# 00_ESP8266_CH340.net
KiCad netlist of a schematic drawn in Altium Designer
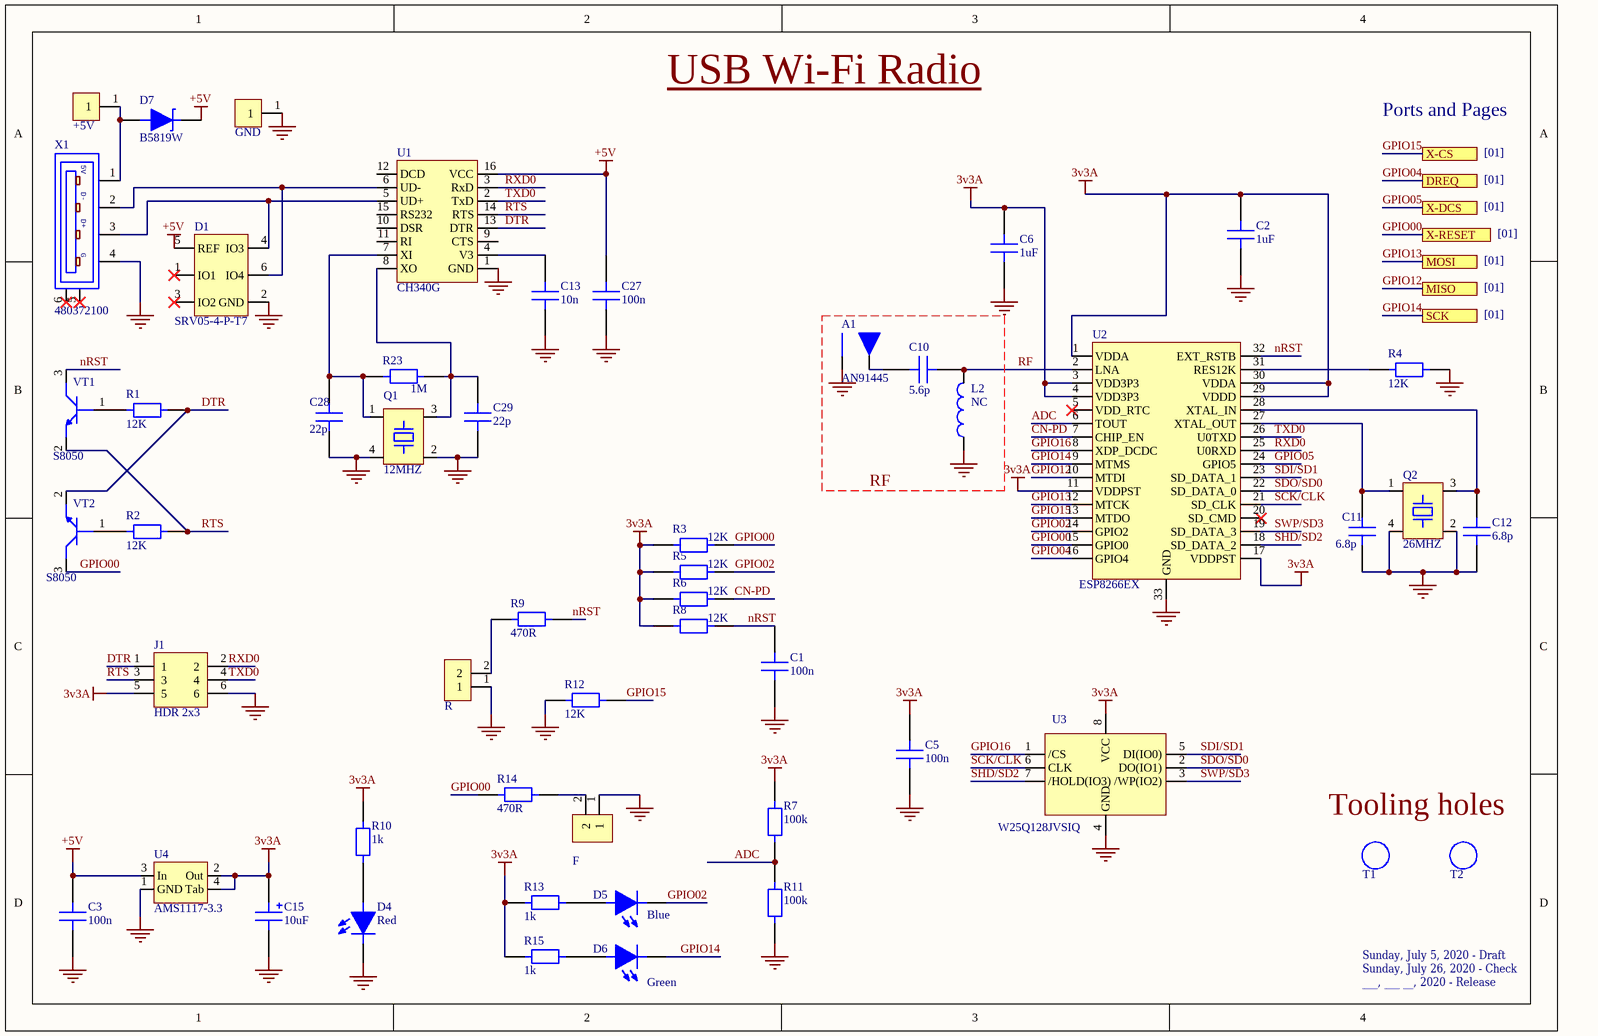
[diagram p0: [00] ESP8266 CH340.SchDoc]

(export (version "E")
  (design (tool "Eeschema 10.0.6"))
  (components
    (comp (ref "A1")
      (value "AN91445")
      (footprint "MIFA 2.4GHz")
      (libsource (lib "WiFi_Lib") (part "MIFA 2.4GHz"))
    )
    (comp (ref "C1")
      (value "100n")
      (footprint "0603 CAP")
      (description "MULTILAYER CERAMIC CAPACITORS MLCC - SMD/SMT 100NF 50V 0603 ROHS")
      (fields (field (name "MANUFACTURER") "YAGEO") (field (name "MFR.PART #") "CC0603KRX7R9BB104"))
      (libsource (lib "JLC_Lib") (part "CC0603KRX7R9BB104"))
    )
    (comp (ref "C2")
      (value "1uF")
      (footprint "0402")
      (description "MULTILAYER CERAMIC CAPACITORS MLCC - SMD/SMT 1UF 25V 0402 ROHS")
      (fields
        (field (name "MANUFACTURER") "Samsung Electro-Mechanics")
        (field (name "MFR.PART #") "CL05A105KA5NQNC")
      )
      (libsource (lib "JLC_Lib") (part "CL05A105KA5NQNC"))
    )
    (comp (ref "C3")
      (value "100n")
      (footprint "0603 CAP")
      (description "MULTILAYER CERAMIC CAPACITORS MLCC - SMD/SMT 100NF 50V 0603 ROHS")
      (fields (field (name "MANUFACTURER") "YAGEO") (field (name "MFR.PART #") "CC0603KRX7R9BB104"))
      (libsource (lib "JLC_Lib") (part "CC0603KRX7R9BB104"))
    )
    (comp (ref "C5")
      (value "100n")
      (footprint "0603 CAP")
      (description "MULTILAYER CERAMIC CAPACITORS MLCC - SMD/SMT 100NF 50V 0603 ROHS")
      (fields (field (name "MANUFACTURER") "YAGEO") (field (name "MFR.PART #") "CC0603KRX7R9BB104"))
      (libsource (lib "JLC_Lib") (part "CC0603KRX7R9BB104"))
    )
    (comp (ref "C6")
      (value "1uF")
      (footprint "0402")
      (description "MULTILAYER CERAMIC CAPACITORS MLCC - SMD/SMT 1UF 25V 0402 ROHS")
      (fields
        (field (name "MANUFACTURER") "Samsung Electro-Mechanics")
        (field (name "MFR.PART #") "CL05A105KA5NQNC")
      )
      (libsource (lib "JLC_Lib") (part "CL05A105KA5NQNC"))
    )
    (comp (ref "C10")
      (value "5.6p")
      (footprint "CAP 0402")
      (description "5.6PF ±0.25PF 50V C0G 0402 MULTILAYER CERAMIC CAPACITORS MLCC - SMD/SMT ROHS")
      (fields
        (field (name "MANUFACTURER") "Samsung Electro-Mechanics")
        (field (name "MFR.PART #") "CL05C5R6CB5NNNC")
      )
      (libsource (lib "JLC_Lib") (part "CL05B103KB5NNNC_1"))
    )
    (comp (ref "C11")
      (value "6.8p")
      (footprint "0402")
      (description "MULTILAYER CERAMIC CAPACITORS MLCC - SMD/SMT 6.8PF 50V 0402 ROHS")
      (fields
        (field (name "MANUFACTURER") "Guangdong Fenghua Advanced Tech")
        (field (name "MFR.PART #") "0402CG6R8C500NT")
      )
      (libsource (lib "JLC_Lib") (part "0402CG6R8C500NT"))
    )
    (comp (ref "C12")
      (value "6.8p")
      (footprint "0402")
      (description "MULTILAYER CERAMIC CAPACITORS MLCC - SMD/SMT 6.8PF 50V 0402 ROHS")
      (fields
        (field (name "MANUFACTURER") "Guangdong Fenghua Advanced Tech")
        (field (name "MFR.PART #") "0402CG6R8C500NT")
      )
      (libsource (lib "JLC_Lib") (part "0402CG6R8C500NT"))
    )
    (comp (ref "C13")
      (value "10n")
      (footprint "0603 CAP")
      (description "MULTILAYER CERAMIC CAPACITORS MLCC - SMD/SMT 10NF 50V 0603 ROHS")
      (fields
        (field (name "MANUFACTURER") "Guangdong Fenghua Advanced Tech")
        (field (name "MFR.PART #") "0603B103K500NT")
      )
      (libsource (lib "JLC_Lib") (part "0603B103K500NT"))
    )
    (comp (ref "C15")
      (value "10uF")
      (footprint "CAP 1206")
      (description "TANTALUM CAPACITORS 10UF 16V CASE-A_3216 ROHS")
      (fields (field (name "MANUFACTURER") "AVX") (field (name "MFR.PART #") "TAJA106K016RNJ"))
      (libsource (lib "JLC_Lib") (part "TAJA106K016RNJ"))
    )
    (comp (ref "C27")
      (value "100n")
      (footprint "0603 CAP")
      (description "MULTILAYER CERAMIC CAPACITORS MLCC - SMD/SMT 100NF 50V 0603 ROHS")
      (fields (field (name "MANUFACTURER") "YAGEO") (field (name "MFR.PART #") "CC0603KRX7R9BB104"))
      (libsource (lib "JLC_Lib") (part "CC0603KRX7R9BB104"))
    )
    (comp (ref "C28")
      (value "22p")
      (footprint "0603 CAP")
      (description "MULTILAYER CERAMIC CAPACITORS MLCC - SMD/SMT 22PF 50V 0603 ROHS")
      (fields
        (field (name "MANUFACTURER") "Samsung Electro-Mechanics")
        (field (name "MFR.PART #") "CL10C220JB8NNNC")
      )
      (libsource (lib "JLC_Lib") (part "CL10C220JB8NNNC"))
    )
    (comp (ref "C29")
      (value "22p")
      (footprint "0603 CAP")
      (description "MULTILAYER CERAMIC CAPACITORS MLCC - SMD/SMT 22PF 50V 0603 ROHS")
      (fields
        (field (name "MANUFACTURER") "Samsung Electro-Mechanics")
        (field (name "MFR.PART #") "CL10C220JB8NNNC")
      )
      (libsource (lib "JLC_Lib") (part "CL10C220JB8NNNC"))
    )
    (comp (ref "D1")
      (value "SRV05-4-P-T7")
      (footprint "SOT-23-6")
      (description "TVS SOT-23-6 ROHS")
      (fields (field (name "MANUFACTURER") "ProTek Devices") (field (name "LCSC PART #") "C85364"))
      (libsource (lib "JLC_Lib") (part "SRV05-4-P-T7"))
    )
    (comp (ref "D4")
      (value "Red")
      (footprint "LED 0603")
      (description "LIGHT EMITTING DIODES (LED) RED 520~625NM 90~100MCD@20MA TOP VIEW 0603 ROHS")
      (fields (field (name "MANUFACTURER") "Hubei KENTO Elec") (field (name "MFR.PART #") "KT-0603R"))
      (libsource (lib "JLC_Lib") (part "KT-0603R"))
    )
    (comp (ref "D5")
      (value "Blue")
      (footprint "LED 0603")
      (description "LIGHT EMITTING DIODES (LED) BLUE 465~475NM 11.5~28.5MCD@5MA TOP VIEW 0603 ROHS")
      (fields
        (field (name "MANUFACTURER") "Everlight Elec")
        (field (name "MFR.PART #") "19-217/BHC-ZL1M2RY/3T")
      )
      (libsource (lib "JLC_Lib") (part "19-217/BHC-ZL1M2RY/3T"))
    )
    (comp (ref "D6")
      (value "Green")
      (footprint "LED 0603")
      (description "LIGHT EMITTING DIODES (LED) GREEN 520~535NM 112~258MCD@20MA TOP VIEW 0603 ROHS")
      (fields
        (field (name "MANUFACTURER") "Everlight Elec")
        (field (name "MFR.PART #") "19-217/GHC-YR1S2/3T")
      )
      (libsource (lib "JLC_Lib") (part "19-217/GHC-YR1S2/3T"))
    )
    (comp (ref "D7")
      (value "B5819W")
      (footprint "SOD-123")
      (description "SCHOTTKY BARRIER DIODES (SBD) SOD-123 ROHS")
      (fields
        (field (name "MANUFACTURER") "Changjiang Electronics Tech (CJ)")
        (field (name "LCSC PART #") "C8598")
      )
      (libsource (lib "JLC_Lib") (part "B5819W"))
    )
    (comp (ref "J1")
      (value "HDR 2x3")
      (footprint "HDR 2x3 2.54mm")
      (description "CONN HEADER 6POS .100 STR 30AU")
      (libsource (lib "WiFi_Lib") (part "67997-106HLF"))
    )
    (comp (ref "JP1")
      (value "R")
      (footprint "Hdr_Fem_1x2_2.54mm")
      (description "CONN HEADER VERT 2POS 2.54MM")
      (libsource (lib "") (part "68602-204HLF_1"))
    )
    (comp (ref "JP2")
      (value "F")
      (footprint "Hdr_Fem_1x2_2.54mm")
      (description "CONN HEADER VERT 2POS 2.54MM")
      (libsource (lib "WiFi_Lib") (part "68602-204HLF"))
    )
    (comp (ref "JP3")
      (value "+5V")
      (footprint "Hdr_Fem_1x1_2.54mm")
      (description "CONN HEADER VERT 1POS 2.54MM")
      (libsource (lib "WiFi_Lib") (part "68602-101HLF"))
    )
    (comp (ref "JP4")
      (value "GND")
      (footprint "Hdr_Fem_1x1_2.54mm")
      (description "CONN HEADER VERT 1POS 2.54MM")
      (libsource (lib "WiFi_Lib") (part "68602-101HLF"))
    )
    (comp (ref "L2")
      (value "NC")
      (footprint "IND 0402")
      (description "IND 0402 Matching")
      (libsource (lib "WiFi_Lib") (part "NC IND"))
    )
    (comp (ref "Q1")
      (value "12MHZ")
      (footprint "ABM8W")
      (description "SMD CRYSTAL RESONATORS 12MHZ ±10PPM SMD-3225_4P ROHS")
      (fields (field (name "MANUFACTURER") "Yangxing Tech") (field (name "MFR.PART #") "X322512MSB4SI"))
      (libsource (lib "JLC_Lib") (part "X322512MSB4SI"))
    )
    (comp (ref "Q2")
      (value "26MHZ")
      (footprint "ABM8W")
      (description "SMD CRYSTAL RESONATORS 26MHZ ±10PPM SMD-3225_4P ROHS")
      (fields (field (name "MANUFACTURER") "Yangxing Tech") (field (name "MFR.PART #") "X322526MEB4SC"))
      (libsource (lib "JLC_Lib") (part "X322526MEB4SC"))
    )
    (comp (ref "R1")
      (value "12K")
      (footprint "0603 RES")
      (description "CHIP RESISTOR - SURFACE MOUNT 12KOHMS ±1% 1/10W 0603 ROHS")
      (fields (field (name "MANUFACTURER") "Uniroyal Elec") (field (name "MFR.PART #") "0603WAF1202T5E"))
      (libsource (lib "JLC_Lib") (part "0603WAF1202T5E"))
    )
    (comp (ref "R2")
      (value "12K")
      (footprint "0603 RES")
      (description "CHIP RESISTOR - SURFACE MOUNT 12KOHMS ±1% 1/10W 0603 ROHS")
      (fields (field (name "MANUFACTURER") "Uniroyal Elec") (field (name "MFR.PART #") "0603WAF1202T5E"))
      (libsource (lib "JLC_Lib") (part "0603WAF1202T5E"))
    )
    (comp (ref "R3")
      (value "12K")
      (footprint "0603 RES")
      (description "CHIP RESISTOR - SURFACE MOUNT 12KOHMS ±1% 1/10W 0603 ROHS")
      (fields (field (name "MANUFACTURER") "Uniroyal Elec") (field (name "MFR.PART #") "0603WAF1202T5E"))
      (libsource (lib "JLC_Lib") (part "0603WAF1202T5E"))
    )
    (comp (ref "R4")
      (value "12K")
      (footprint "0402 RES")
      (description "CHIP RESISTOR - SURFACE MOUNT 12KOHMS ±1% 1/16W 0402 ROHS")
      (fields (field (name "MANUFACTURER") "Uniroyal Elec") (field (name "MFR.PART #") "0402WGF1202TCE"))
      (libsource (lib "JLC_Lib") (part "0402WGF1202TCE"))
    )
    (comp (ref "R5")
      (value "12K")
      (footprint "0603 RES")
      (description "CHIP RESISTOR - SURFACE MOUNT 12KOHMS ±1% 1/10W 0603 ROHS")
      (fields (field (name "MANUFACTURER") "Uniroyal Elec") (field (name "MFR.PART #") "0603WAF1202T5E"))
      (libsource (lib "JLC_Lib") (part "0603WAF1202T5E"))
    )
    (comp (ref "R6")
      (value "12K")
      (footprint "0603 RES")
      (description "CHIP RESISTOR - SURFACE MOUNT 12KOHMS ±1% 1/10W 0603 ROHS")
      (fields (field (name "MANUFACTURER") "Uniroyal Elec") (field (name "MFR.PART #") "0603WAF1202T5E"))
      (libsource (lib "JLC_Lib") (part "0603WAF1202T5E"))
    )
    (comp (ref "R7")
      (value "100k")
      (footprint "0603 RES")
      (description "CHIP RESISTOR - SURFACE MOUNT 100KOHMS ±1% 1/10W 0603 ROHS")
      (fields (field (name "MANUFACTURER") "Uniroyal Elec") (field (name "MFR.PART #") "0603WAF1003T5E"))
      (libsource (lib "JLC_Lib") (part "0603WAF1003T5E"))
    )
    (comp (ref "R8")
      (value "12K")
      (footprint "0603 RES")
      (description "CHIP RESISTOR - SURFACE MOUNT 12KOHMS ±1% 1/10W 0603 ROHS")
      (fields (field (name "MANUFACTURER") "Uniroyal Elec") (field (name "MFR.PART #") "0603WAF1202T5E"))
      (libsource (lib "JLC_Lib") (part "0603WAF1202T5E"))
    )
    (comp (ref "R9")
      (value "470R")
      (footprint "0603 RES")
      (description "CHIP RESISTOR - SURFACE MOUNT 470OHMS ±1% 1/10W 0603 ROHS")
      (fields (field (name "MANUFACTURER") "Uniroyal Elec") (field (name "MFR.PART #") "0603WAF4700T5E"))
      (libsource (lib "JLC_Lib") (part "0603WAF4700T5E"))
    )
    (comp (ref "R10")
      (value "1k")
      (footprint "0603 RES")
      (description "CHIP RESISTOR - SURFACE MOUNT 1KOHMS ±1% 1/10W 0603 ROHS")
      (fields (field (name "MANUFACTURER") "Uniroyal Elec") (field (name "MFR.PART #") "0603WAF1001T5E"))
      (libsource (lib "JLC_Lib") (part "0603WAF1001T5E"))
    )
    (comp (ref "R11")
      (value "100k")
      (footprint "0603 RES")
      (description "CHIP RESISTOR - SURFACE MOUNT 100KOHMS ±1% 1/10W 0603 ROHS")
      (fields (field (name "MANUFACTURER") "Uniroyal Elec") (field (name "MFR.PART #") "0603WAF1003T5E"))
      (libsource (lib "JLC_Lib") (part "0603WAF1003T5E"))
    )
    (comp (ref "R12")
      (value "12K")
      (footprint "0603 RES")
      (description "CHIP RESISTOR - SURFACE MOUNT 12KOHMS ±1% 1/10W 0603 ROHS")
      (fields (field (name "MANUFACTURER") "Uniroyal Elec") (field (name "MFR.PART #") "0603WAF1202T5E"))
      (libsource (lib "JLC_Lib") (part "0603WAF1202T5E"))
    )
    (comp (ref "R13")
      (value "1k")
      (footprint "0603 RES")
      (description "CHIP RESISTOR - SURFACE MOUNT 1KOHMS ±1% 1/10W 0603 ROHS")
      (fields (field (name "MANUFACTURER") "Uniroyal Elec") (field (name "MFR.PART #") "0603WAF1001T5E"))
      (libsource (lib "JLC_Lib") (part "0603WAF1001T5E"))
    )
    (comp (ref "R14")
      (value "470R")
      (footprint "0603 RES")
      (description "CHIP RESISTOR - SURFACE MOUNT 470OHMS ±1% 1/10W 0603 ROHS")
      (fields (field (name "MANUFACTURER") "Uniroyal Elec") (field (name "MFR.PART #") "0603WAF4700T5E"))
      (libsource (lib "JLC_Lib") (part "0603WAF4700T5E"))
    )
    (comp (ref "R15")
      (value "1k")
      (footprint "0603 RES")
      (description "CHIP RESISTOR - SURFACE MOUNT 1KOHMS ±1% 1/10W 0603 ROHS")
      (fields (field (name "MANUFACTURER") "Uniroyal Elec") (field (name "MFR.PART #") "0603WAF1001T5E"))
      (libsource (lib "JLC_Lib") (part "0603WAF1001T5E"))
    )
    (comp (ref "R23")
      (value "1M")
      (footprint "0603 RES")
      (description "CHIP RESISTOR - SURFACE MOUNT 1MOHMS ±1% 1/10W 0603 ROHS")
      (fields (field (name "MANUFACTURER") "Uniroyal Elec") (field (name "MFR.PART #") "0603WAF1004T5E"))
      (libsource (lib "JLC_Lib") (part "0603WAF1004T5E"))
    )
    (comp (ref "T1")
      (value "Tooling hole")
      (footprint "Tooling")
      (description "For JLCPCB SMT Assembly")
      (libsource (lib "JLC_Lib") (part "Tooling hole"))
    )
    (comp (ref "T2")
      (value "Tooling hole")
      (footprint "Tooling")
      (description "For JLCPCB SMT Assembly")
      (libsource (lib "JLC_Lib") (part "Tooling hole"))
    )
    (comp (ref "U1")
      (value "CH340G")
      (footprint "SOP-16")
      (description "USB 2MBPS 3.3V, 5V SOP-16_150MIL ROHS")
      (fields (field (name "MANUFACTURER") "Jiangsu Qin Heng") (field (name "LCSC PART #") "C14267"))
      (libsource (lib "JLC_Lib") (part "CH340G"))
    )
    (comp (ref "U2")
      (value "ESP8266EX")
      (footprint "QFN-32 Thermal")
      (fields (field (name "MANUFACTURER") "Espressif Systems") (field (name "LCSC PART #") "C77967"))
      (libsource (lib "JLC_Lib") (part "ESP8266EX"))
    )
    (comp (ref "U3")
      (value "W25Q128JVSIQ")
      (footprint "SOIC-8 208-mil")
      (description "FLASH FLASH 128MB (16M X 8) SPI - DUAL/QUAD I/O SOIC-8_208MIL ROHS")
      (fields (field (name "MANUFACTURER") "Winbond Elec") (field (name "LCSC PART #") "C97521"))
      (libsource (lib "JLC_Lib") (part "W25Q128JVSIQ"))
    )
    (comp (ref "U4")
      (value "AMS1117-3.3")
      (footprint "SOT233-3")
      (description "LOW DROPOUT REGULATORS(LDO) POSITIVE FIXED 1.3V @ 800MA 15V 3.3V 1A SOT-223 ROHS")
      (fields
        (field (name "MANUFACTURER") "Advanced Monolithic Systems")
        (field (name "LCSC PART #") "C6186")
      )
      (libsource (lib "JLC_Lib") (part "AMS1117-3.3"))
    )
    (comp (ref "VT1")
      (value "S8050")
      (footprint "SOT-23")
      (description "TRANSISTORS (NPN/PNP) NPN 500MA 25V SOT-23(SOT-23-3) ROHS")
      (fields
        (field (name "MANUFACTURER") "Changjiang Electronics Tech (CJ)")
        (field (name "LCSC PART #") "C2146")
      )
      (libsource (lib "JLC_Lib") (part "S8050"))
    )
    (comp (ref "VT2")
      (value "S8050")
      (footprint "SOT-23")
      (description "TRANSISTORS (NPN/PNP) NPN 500MA 25V SOT-23(SOT-23-3) ROHS")
      (fields
        (field (name "MANUFACTURER") "Changjiang Electronics Tech (CJ)")
        (field (name "LCSC PART #") "C2146")
      )
      (libsource (lib "JLC_Lib") (part "S8050"))
    )
    (comp (ref "X1")
      (value "480372100")
      (footprint "USB2.0-A")
      (description "USB - Type A Male USB 2 4 Through Hole USB Connectors RoHS")
      (fields (field (name "MANUFACTURER") "MOLEX") (field (name "LCSC PART #") "C136453"))
      (libsource (lib "JLC_Lib") (part "480372100"))
    )
  )
  (nets
    (net (code "1") (name "+5V") (class "Default")
      (node (ref "C27") (pin "2") (pinfunction "2_2") (pintype "passive"))
      (node (ref "C3") (pin "2") (pinfunction "2_2") (pintype "passive"))
      (node (ref "D1") (pin "5") (pinfunction "REF_5") (pintype "passive"))
      (node (ref "D7") (pin "2") (pinfunction "K_2") (pintype "passive"))
      (node (ref "U1") (pin "16") (pinfunction "VCC_16") (pintype "passive"))
      (node (ref "U4") (pin "3") (pinfunction "In_3") (pintype "passive"))
    )
    (net (code "2") (name "/ADC") (class "Default")
      (node (ref "R11") (pin "2") (pinfunction "2_2") (pintype "passive"))
      (node (ref "R7") (pin "1") (pinfunction "1_1") (pintype "passive"))
      (node (ref "U2") (pin "6") (pinfunction "TOUT_6") (pintype "passive"))
    )
    (net (code "3") (name "/CN-PD") (class "Default")
      (node (ref "R6") (pin "2") (pinfunction "2_2") (pintype "passive"))
      (node (ref "U2") (pin "7") (pinfunction "CHIP_EN_7") (pintype "passive"))
    )
    (net (code "4") (name "/DTR") (class "Default")
      (node (ref "J1") (pin "1") (pinfunction "1_1") (pintype "passive"))
      (node (ref "R1") (pin "2") (pinfunction "2_2") (pintype "passive"))
      (node (ref "U1") (pin "13") (pinfunction "DTR_13") (pintype "passive"))
      (node (ref "VT2") (pin "2") (pinfunction "2_2") (pintype "passive"))
    )
    (net (code "5") (name "/GPIO00") (class "Default")
      (node (ref "R14") (pin "1") (pinfunction "1_1") (pintype "passive"))
      (node (ref "R3") (pin "2") (pinfunction "2_2") (pintype "passive"))
      (node (ref "U2") (pin "15") (pinfunction "GPIO0_15") (pintype "passive"))
      (node (ref "VT2") (pin "3") (pinfunction "3_3") (pintype "passive"))
    )
    (net (code "6") (name "/GPIO02") (class "Default")
      (node (ref "D5") (pin "2") (pinfunction "2_2") (pintype "passive"))
      (node (ref "R5") (pin "2") (pinfunction "2_2") (pintype "passive"))
      (node (ref "U2") (pin "14") (pinfunction "GPIO2_14") (pintype "passive"))
    )
    (net (code "7") (name "/GPIO04") (class "Default")
      (node (ref "U2") (pin "16") (pinfunction "GPIO4_16") (pintype "passive"))
    )
    (net (code "8") (name "/GPIO05") (class "Default")
      (node (ref "U2") (pin "24") (pinfunction "GPIO5_24") (pintype "passive"))
    )
    (net (code "9") (name "/GPIO12") (class "Default")
      (node (ref "U2") (pin "10") (pinfunction "MTDI_10") (pintype "passive"))
    )
    (net (code "10") (name "/GPIO13") (class "Default")
      (node (ref "U2") (pin "12") (pinfunction "MTCK_12") (pintype "passive"))
    )
    (net (code "11") (name "/GPIO14") (class "Default")
      (node (ref "D6") (pin "2") (pinfunction "2_2") (pintype "passive"))
      (node (ref "U2") (pin "9") (pinfunction "MTMS_9") (pintype "passive"))
    )
    (net (code "12") (name "/GPIO15") (class "Default")
      (node (ref "R12") (pin "2") (pinfunction "2_2") (pintype "passive"))
      (node (ref "U2") (pin "13") (pinfunction "MTDO_13") (pintype "passive"))
    )
    (net (code "13") (name "/GPIO16") (class "Default")
      (node (ref "U2") (pin "8") (pinfunction "XDP_DCDC_8") (pintype "passive"))
      (node (ref "U3") (pin "1") (pinfunction "/CS_1") (pintype "passive"))
    )
    (net (code "14") (name "/RF") (class "Default")
      (node (ref "C10") (pin "2") (pinfunction "2_2") (pintype "passive"))
      (node (ref "L2") (pin "2") (pinfunction "2_2") (pintype "passive"))
      (node (ref "U2") (pin "2") (pinfunction "LNA_2") (pintype "passive"))
    )
    (net (code "15") (name "/RTS") (class "Default")
      (node (ref "J1") (pin "3") (pinfunction "3_3") (pintype "passive"))
      (node (ref "R2") (pin "2") (pinfunction "2_2") (pintype "passive"))
      (node (ref "U1") (pin "14") (pinfunction "RTS_14") (pintype "passive"))
      (node (ref "VT1") (pin "2") (pinfunction "2_2") (pintype "passive"))
    )
    (net (code "16") (name "/RXD0") (class "Default")
      (node (ref "J1") (pin "2") (pinfunction "2_2") (pintype "passive"))
      (node (ref "U1") (pin "3") (pinfunction "RxD_3") (pintype "passive"))
      (node (ref "U2") (pin "25") (pinfunction "U0RXD_25") (pintype "passive"))
    )
    (net (code "17") (name "/SCK{slash}CLK") (class "Default")
      (node (ref "U2") (pin "21") (pinfunction "SD_CLK_21") (pintype "passive"))
      (node (ref "U3") (pin "6") (pinfunction "CLK_6") (pintype "passive"))
    )
    (net (code "18") (name "/SDI{slash}SD1") (class "Default")
      (node (ref "U2") (pin "23") (pinfunction "SD_DATA_1_23") (pintype "passive"))
      (node (ref "U3") (pin "5") (pinfunction "DI(IO0)_5") (pintype "passive"))
    )
    (net (code "19") (name "/SDO{slash}SD0") (class "Default")
      (node (ref "U2") (pin "22") (pinfunction "SD_DATA_0_22") (pintype "passive"))
      (node (ref "U3") (pin "2") (pinfunction "DO(IO1)_2") (pintype "passive"))
    )
    (net (code "20") (name "/SHD{slash}SD2") (class "Default")
      (node (ref "U2") (pin "18") (pinfunction "SD_DATA_2_18") (pintype "passive"))
      (node (ref "U3") (pin "7") (pinfunction "/HOLD(IO3)_7") (pintype "passive"))
    )
    (net (code "21") (name "/SWP{slash}SD3") (class "Default")
      (node (ref "U2") (pin "19") (pinfunction "SD_DATA_3_19") (pintype "passive"))
      (node (ref "U3") (pin "3") (pinfunction "/WP(IO2)_3") (pintype "passive"))
    )
    (net (code "22") (name "/TXD0") (class "Default")
      (node (ref "J1") (pin "4") (pinfunction "4_4") (pintype "passive"))
      (node (ref "U1") (pin "2") (pinfunction "TxD_2") (pintype "passive"))
      (node (ref "U2") (pin "26") (pinfunction "U0TXD_26") (pintype "passive"))
    )
    (net (code "23") (name "/nRST") (class "Default")
      (node (ref "C1") (pin "2") (pinfunction "2_2") (pintype "passive"))
      (node (ref "R8") (pin "2") (pinfunction "2_2") (pintype "passive"))
      (node (ref "R9") (pin "2") (pinfunction "2_2") (pintype "passive"))
      (node (ref "U2") (pin "32") (pinfunction "EXT_RSTB_32") (pintype "passive"))
      (node (ref "VT1") (pin "3") (pinfunction "3_3") (pintype "passive"))
    )
    (net (code "24") (name "3v3A") (class "Default")
      (node (ref "C15") (pin "1") (pinfunction "1_1") (pintype "passive"))
      (node (ref "C2") (pin "2") (pinfunction "2_2") (pintype "passive"))
      (node (ref "C5") (pin "1") (pinfunction "1_1") (pintype "passive"))
      (node (ref "C6") (pin "2") (pinfunction "2_2") (pintype "passive"))
      (node (ref "J1") (pin "5") (pinfunction "5_5") (pintype "passive"))
      (node (ref "R10") (pin "2") (pinfunction "2_2") (pintype "passive"))
      (node (ref "R13") (pin "1") (pinfunction "1_1") (pintype "passive"))
      (node (ref "R15") (pin "1") (pinfunction "1_1") (pintype "passive"))
      (node (ref "R3") (pin "1") (pinfunction "1_1") (pintype "passive"))
      (node (ref "R5") (pin "1") (pinfunction "1_1") (pintype "passive"))
      (node (ref "R6") (pin "1") (pinfunction "1_1") (pintype "passive"))
      (node (ref "R7") (pin "2") (pinfunction "2_2") (pintype "passive"))
      (node (ref "R8") (pin "1") (pinfunction "1_1") (pintype "passive"))
      (node (ref "U2") (pin "1") (pinfunction "VDDA_1") (pintype "passive"))
      (node (ref "U2") (pin "11") (pinfunction "VDDPST_11") (pintype "passive"))
      (node (ref "U2") (pin "17") (pinfunction "VDDPST_17") (pintype "passive"))
      (node (ref "U2") (pin "29") (pinfunction "VDDD_29") (pintype "passive"))
      (node (ref "U2") (pin "3") (pinfunction "VDD3P3_3") (pintype "passive"))
      (node (ref "U2") (pin "30") (pinfunction "VDDA_30") (pintype "passive"))
      (node (ref "U2") (pin "4") (pinfunction "VDD3P3_4") (pintype "passive"))
      (node (ref "U3") (pin "8") (pinfunction "VCC_8") (pintype "passive"))
      (node (ref "U4") (pin "2") (pinfunction "Out_2") (pintype "passive"))
      (node (ref "U4") (pin "4") (pinfunction "Tab_4") (pintype "passive"))
    )
    (net (code "25") (name "GND") (class "Default")
      (node (ref "A1") (pin "2") (pinfunction "2_2") (pintype "passive"))
      (node (ref "C1") (pin "1") (pinfunction "1_1") (pintype "passive"))
      (node (ref "C11") (pin "1") (pinfunction "1_1") (pintype "passive"))
      (node (ref "C12") (pin "1") (pinfunction "1_1") (pintype "passive"))
      (node (ref "C13") (pin "1") (pinfunction "1_1") (pintype "passive"))
      (node (ref "C15") (pin "2") (pinfunction "2_2") (pintype "passive"))
      (node (ref "C2") (pin "1") (pinfunction "1_1") (pintype "passive"))
      (node (ref "C27") (pin "1") (pinfunction "1_1") (pintype "passive"))
      (node (ref "C28") (pin "1") (pinfunction "1_1") (pintype "passive"))
      (node (ref "C29") (pin "1") (pinfunction "1_1") (pintype "passive"))
      (node (ref "C3") (pin "1") (pinfunction "1_1") (pintype "passive"))
      (node (ref "C5") (pin "2") (pinfunction "2_2") (pintype "passive"))
      (node (ref "C6") (pin "1") (pinfunction "1_1") (pintype "passive"))
      (node (ref "D1") (pin "2") (pinfunction "GND_2") (pintype "passive"))
      (node (ref "D4") (pin "2") (pinfunction "2_2") (pintype "passive"))
      (node (ref "J1") (pin "6") (pinfunction "6_6") (pintype "passive"))
      (node (ref "JP1") (pin "1") (pinfunction "1_1") (pintype "passive"))
      (node (ref "JP2") (pin "1") (pinfunction "1_1") (pintype "passive"))
      (node (ref "JP4") (pin "1") (pinfunction "1_1") (pintype "passive"))
      (node (ref "L2") (pin "1") (pinfunction "1_1") (pintype "passive"))
      (node (ref "Q1") (pin "2") (pinfunction "GND_2") (pintype "passive"))
      (node (ref "Q1") (pin "4") (pinfunction "GND_4") (pintype "passive"))
      (node (ref "Q2") (pin "2") (pinfunction "GND_2") (pintype "passive"))
      (node (ref "Q2") (pin "4") (pinfunction "GND_4") (pintype "passive"))
      (node (ref "R11") (pin "1") (pinfunction "1_1") (pintype "passive"))
      (node (ref "R12") (pin "1") (pinfunction "1_1") (pintype "passive"))
      (node (ref "R4") (pin "2") (pinfunction "2_2") (pintype "passive"))
      (node (ref "U1") (pin "1") (pinfunction "GND_1") (pintype "passive"))
      (node (ref "U2") (pin "33") (pinfunction "GND_33") (pintype "passive"))
      (node (ref "U3") (pin "4") (pinfunction "GND_4") (pintype "passive"))
      (node (ref "U4") (pin "1") (pinfunction "GND_1") (pintype "passive"))
      (node (ref "X1") (pin "4") (pinfunction "GND_4") (pintype "passive"))
    )
    (net (code "26") (name "Net-(A1-Pad1)") (class "Default")
      (node (ref "A1") (pin "1") (pinfunction "1_1") (pintype "passive"))
      (node (ref "C10") (pin "1") (pinfunction "1_1") (pintype "passive"))
    )
    (net (code "27") (name "Net-(D1-IO3)") (class "Default")
      (node (ref "D1") (pin "4") (pinfunction "IO3_4") (pintype "passive"))
      (node (ref "U1") (pin "5") (pinfunction "UD+_5") (pintype "passive"))
      (node (ref "X1") (pin "3") (pinfunction "DX_P_3") (pintype "passive"))
    )
    (net (code "28") (name "Net-(D1-IO4)") (class "Default")
      (node (ref "D1") (pin "6") (pinfunction "IO4_6") (pintype "passive"))
      (node (ref "U1") (pin "6") (pinfunction "UD-_6") (pintype "passive"))
      (node (ref "X1") (pin "2") (pinfunction "DX_N_2") (pintype "passive"))
    )
    (net (code "29") (name "Net-(D4-Pad1)") (class "Default")
      (node (ref "D4") (pin "1") (pinfunction "1_1") (pintype "passive"))
      (node (ref "R10") (pin "1") (pinfunction "1_1") (pintype "passive"))
    )
    (net (code "30") (name "Net-(D5-Pad1)") (class "Default")
      (node (ref "D5") (pin "1") (pinfunction "1_1") (pintype "passive"))
      (node (ref "R13") (pin "2") (pinfunction "2_2") (pintype "passive"))
    )
    (net (code "31") (name "Net-(D6-Pad1)") (class "Default")
      (node (ref "D6") (pin "1") (pinfunction "1_1") (pintype "passive"))
      (node (ref "R15") (pin "2") (pinfunction "2_2") (pintype "passive"))
    )
    (net (code "32") (name "Net-(D7-A)") (class "Default")
      (node (ref "D7") (pin "1") (pinfunction "A_1") (pintype "passive"))
      (node (ref "JP3") (pin "1") (pinfunction "1_1") (pintype "passive"))
      (node (ref "X1") (pin "1") (pinfunction "5V_1") (pintype "passive"))
    )
    (net (code "33") (name "Net-(JP1-Pad2)") (class "Default")
      (node (ref "JP1") (pin "2") (pinfunction "2_2") (pintype "passive"))
      (node (ref "R9") (pin "1") (pinfunction "1_1") (pintype "passive"))
    )
    (net (code "34") (name "Net-(JP2-Pad2)") (class "Default")
      (node (ref "JP2") (pin "2") (pinfunction "2_2") (pintype "passive"))
      (node (ref "R14") (pin "2") (pinfunction "2_2") (pintype "passive"))
    )
    (net (code "35") (name "Net-(R1-Pad1)") (class "Default")
      (node (ref "R1") (pin "1") (pinfunction "1_1") (pintype "passive"))
      (node (ref "VT1") (pin "1") (pinfunction "1_1") (pintype "passive"))
    )
    (net (code "36") (name "Net-(R2-Pad1)") (class "Default")
      (node (ref "R2") (pin "1") (pinfunction "1_1") (pintype "passive"))
      (node (ref "VT2") (pin "1") (pinfunction "1_1") (pintype "passive"))
    )
    (net (code "37") (name "Net-(U1-V3)") (class "Default")
      (node (ref "C13") (pin "2") (pinfunction "2_2") (pintype "passive"))
      (node (ref "U1") (pin "4") (pinfunction "V3_4") (pintype "passive"))
    )
    (net (code "38") (name "Net-(U1-XI)") (class "Default")
      (node (ref "C28") (pin "2") (pinfunction "2_2") (pintype "passive"))
      (node (ref "Q1") (pin "1") (pinfunction "1_1") (pintype "passive"))
      (node (ref "R23") (pin "1") (pinfunction "1_1") (pintype "passive"))
      (node (ref "U1") (pin "7") (pinfunction "XI_7") (pintype "passive"))
    )
    (net (code "39") (name "Net-(U1-XO)") (class "Default")
      (node (ref "C29") (pin "2") (pinfunction "2_2") (pintype "passive"))
      (node (ref "Q1") (pin "3") (pinfunction "3_3") (pintype "passive"))
      (node (ref "R23") (pin "2") (pinfunction "2_2") (pintype "passive"))
      (node (ref "U1") (pin "8") (pinfunction "XO_8") (pintype "passive"))
    )
    (net (code "40") (name "Net-(U2-RES12K)") (class "Default")
      (node (ref "R4") (pin "1") (pinfunction "1_1") (pintype "passive"))
      (node (ref "U2") (pin "31") (pinfunction "RES12K_31") (pintype "passive"))
    )
    (net (code "41") (name "Net-(U2-XTAL_IN)") (class "Default")
      (node (ref "C12") (pin "2") (pinfunction "2_2") (pintype "passive"))
      (node (ref "Q2") (pin "3") (pinfunction "3_3") (pintype "passive"))
      (node (ref "U2") (pin "28") (pinfunction "XTAL_IN_28") (pintype "passive"))
    )
    (net (code "42") (name "Net-(U2-XTAL_OUT)") (class "Default")
      (node (ref "C11") (pin "2") (pinfunction "2_2") (pintype "passive"))
      (node (ref "Q2") (pin "1") (pinfunction "1_1") (pintype "passive"))
      (node (ref "U2") (pin "27") (pinfunction "XTAL_OUT_27") (pintype "passive"))
    )
    (net (code "43") (name "unconnected-(D1-IO1-Pad1)") (class "Default")
      (node (ref "D1") (pin "1") (pinfunction "IO1_1") (pintype "passive+no_connect"))
    )
    (net (code "44") (name "unconnected-(D1-IO2-Pad3)") (class "Default")
      (node (ref "D1") (pin "3") (pinfunction "IO2_3") (pintype "passive+no_connect"))
    )
    (net (code "45") (name "unconnected-(U1-CTS-Pad9)") (class "Default")
      (node (ref "U1") (pin "9") (pinfunction "CTS_9") (pintype "passive"))
    )
    (net (code "46") (name "unconnected-(U1-DCD-Pad12)") (class "Default")
      (node (ref "U1") (pin "12") (pinfunction "DCD_12") (pintype "passive"))
    )
    (net (code "47") (name "unconnected-(U1-DSR-Pad10)") (class "Default")
      (node (ref "U1") (pin "10") (pinfunction "DSR_10") (pintype "passive"))
    )
    (net (code "48") (name "unconnected-(U1-RI-Pad11)") (class "Default")
      (node (ref "U1") (pin "11") (pinfunction "RI_11") (pintype "passive"))
    )
    (net (code "49") (name "unconnected-(U1-RS232-Pad15)") (class "Default")
      (node (ref "U1") (pin "15") (pinfunction "RS232_15") (pintype "passive"))
    )
    (net (code "50") (name "unconnected-(U2-SD_CMD-Pad20)") (class "Default")
      (node (ref "U2") (pin "20") (pinfunction "SD_CMD_20") (pintype "passive+no_connect"))
    )
    (net (code "51") (name "unconnected-(U2-VDD_RTC-Pad5)") (class "Default")
      (node (ref "U2") (pin "5") (pinfunction "VDD_RTC_5") (pintype "passive+no_connect"))
    )
    (net (code "52") (name "unconnected-(X1-Pad5)") (class "Default")
      (node (ref "X1") (pin "5") (pinfunction "5_5") (pintype "passive+no_connect"))
    )
    (net (code "53") (name "unconnected-(X1-Pad6)") (class "Default")
      (node (ref "X1") (pin "6") (pinfunction "6_6") (pintype "passive+no_connect"))
    )
  )
)
